# MCU_POWER.net
KiCad netlist of a schematic drawn in Altium Designer
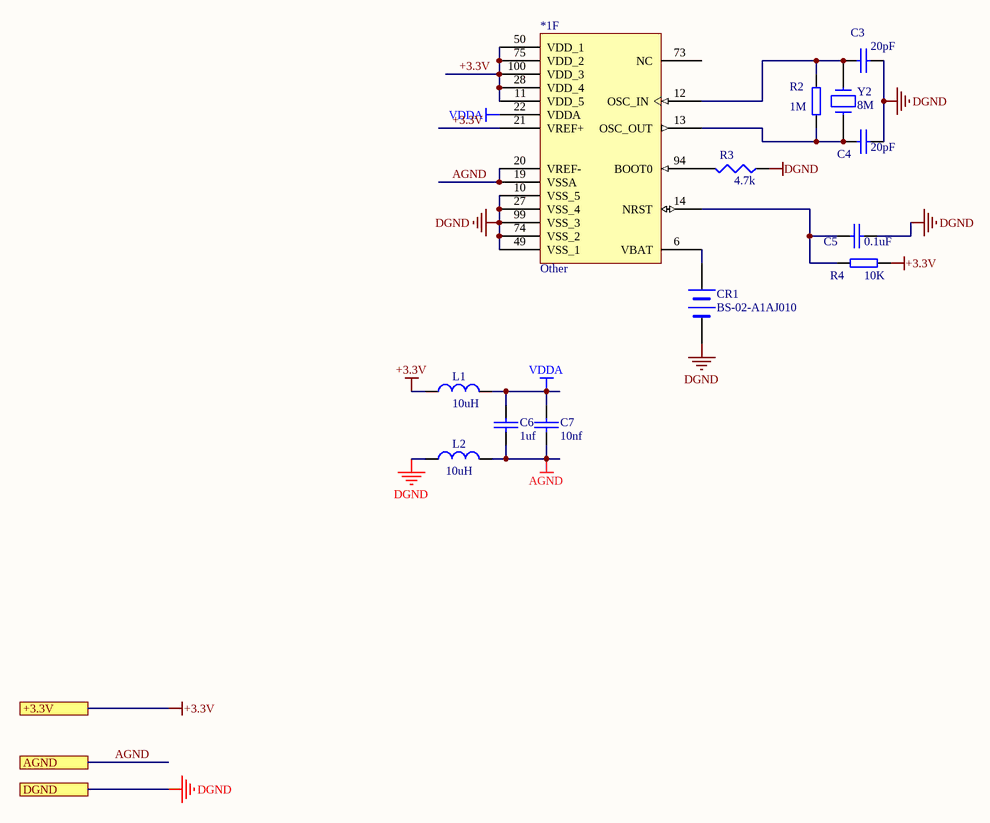
[diagram p0: MCU_POWER.SchDoc]

(export (version "E")
  (design (tool "Eeschema 10.0.6"))
  (components
    (comp (ref "*1")
      (value "Other")
      (footprint "STM-LQFP100_N")
      (libsource (lib "原理图") (part "stm32f103vct6"))
    )
    (comp (ref "C3")
      (value "20pF")
      (footprint "0805C")
      (description "品牌： SAMSUNG(三星)  型号： CL21C200JBANNNC     容值：20pF 精度：±5% 额定电压：50V 材质(温度系数)：C0G 材质:C0G")
      (libsource (lib "SCHPCBLIB ") (part "CAP_3"))
    )
    (comp (ref "C4")
      (value "20pF")
      (footprint "0805C")
      (description "品牌： SAMSUNG(三星)  型号： CL21C200JBANNNC     容值：20pF 精度：±5% 额定电压：50V 材质(温度系数)：C0G 材质:C0G")
      (libsource (lib "SCHPCBLIB ") (part "CAP_3"))
    )
    (comp (ref "C5")
      (value "0.1uF")
      (footprint "0805C")
      (description "品牌： SAMSUNG(三星)    型号： CL10B104KB8NNNC  容值：100nF 精度：±10% 额定电压：50V 材质(温度系数)：X7R 材质:X7R")
      (libsource (lib "SCHPCBLIB ") (part "CAP_3"))
    )
    (comp (ref "C6")
      (value "1uf")
      (footprint "0805C")
      (description "品牌： SAMSUNG(三星)  型号： CL21B105KBFNNNE  容值：1uF 精度：±10% 额定电压：50V 材质(温度系数)：X7R 材质:X7R")
      (libsource (lib "SCHPCBLIB ") (part "CAP_3"))
    )
    (comp (ref "C7")
      (value "10nf")
      (footprint "0805C")
      (description "品牌： SAMSUNG(三星)  型号： CL21B103KBANNNC  容值：10nF 精度：±10% 额定电压：50V 材质(温度系数)：X7R 材质:X7R")
      (libsource (lib "SCHPCBLIB ") (part "CAP_3"))
    )
    (comp (ref "CR1")
      (value "BS-02-A1AJ010")
      (footprint "BATT")
      (description "品牌： MYOUNG(美阳)  型号： BS-02-A1AJ010  连接器类型：电池底座 适用电池规格：CR2032 工作温度范围：-25℃~+85℃ 插脚 卧式底座 环保吸塑托盘包装")
      (libsource (lib "Documents") (part "BATTERY"))
    )
    (comp (ref "L1")
      (value "10uH")
      (footprint "L 0805")
      (description "品牌： FH(风华)  型号： CMI201209X100KT  ：电感值：10uH 精度：±10% 额定电流：15mA 直流电阻(DCR)：1.15Ω")
      (libsource (lib "SCHPCBLIB ") (part "INDUCTOR"))
    )
    (comp (ref "L2")
      (value "10uH")
      (footprint "L 0805")
      (description "品牌： FH(风华)  型号： CMI201209X100KT  ：电感值：10uH 精度：±10% 额定电流：15mA 直流电阻(DCR)：1.15Ω")
      (libsource (lib "SCHPCBLIB ") (part "INDUCTOR"))
    )
    (comp (ref "R2")
      (value "1M")
      (footprint "0805R")
      (description "品牌： UNI-ROYAL(厚声)  型号： 0805W8F1004T5E  电阻类型：厚膜电阻 阻值：1MΩ 精度：±1% 功率：125mW 温度系数：±100ppm/℃")
      (libsource (lib "SCHPCBLIB ") (part "RES4"))
    )
    (comp (ref "R3")
      (value "4.7k")
      (footprint "0805R")
      (description "品牌： UNI-ROYAL(厚声)  品牌： UNI-ROYAL(厚声)  电阻类型：厚膜电阻 阻值：100kΩ 精度：±1% 功率：125mW 温度系数：±100ppm/℃")
      (libsource (lib "*") (part "RES1"))
    )
    (comp (ref "R4")
      (value "10K")
      (footprint "0805R")
      (description "品牌： UNI-ROYAL(厚声) 型号： 0805W8F1002T5E 电阻类型：厚膜电阻 阻值：10kΩ 精度：±1% 功率：125mW 温度系数：±100ppm/℃")
      (libsource (lib "SCHPCBLIB ") (part "RES4"))
    )
    (comp (ref "Y2") (value "8M") (footprint "XTAL3") (libsource (lib "SCHPCBLIB ") (part "XTAL-1")))
  )
  (nets
    (net (code "1") (name "+3.3V") (class "Default")
      (node (ref "*1") (pin "100") (pinfunction "VDD_3_100") (pintype "power_in"))
      (node (ref "*1") (pin "11") (pinfunction "VDD_5_11") (pintype "power_in"))
      (node (ref "*1") (pin "21") (pinfunction "VREF+_21") (pintype "power_in"))
      (node (ref "*1") (pin "28") (pinfunction "VDD_4_28") (pintype "power_in"))
      (node (ref "*1") (pin "50") (pinfunction "VDD_1_50") (pintype "power_in"))
      (node (ref "*1") (pin "75") (pinfunction "VDD_2_75") (pintype "power_in"))
      (node (ref "L1") (pin "1") (pinfunction "1_1") (pintype "passive"))
      (node (ref "R4") (pin "2") (pinfunction "2_2") (pintype "passive"))
    )
    (net (code "2") (name "AGND") (class "Default")
      (node (ref "*1") (pin "19") (pinfunction "VSSA_19") (pintype "power_in"))
      (node (ref "*1") (pin "20") (pinfunction "VREF-_20") (pintype "power_in"))
      (node (ref "C6") (pin "1") (pinfunction "1_1") (pintype "passive"))
      (node (ref "C7") (pin "2") (pinfunction "2_2") (pintype "passive"))
      (node (ref "L2") (pin "2") (pinfunction "2_2") (pintype "passive"))
    )
    (net (code "3") (name "DGND") (class "Default")
      (node (ref "*1") (pin "10") (pinfunction "VSS_5_10") (pintype "power_in"))
      (node (ref "*1") (pin "27") (pinfunction "VSS_4_27") (pintype "power_in"))
      (node (ref "*1") (pin "49") (pinfunction "VSS_1_49") (pintype "power_in"))
      (node (ref "*1") (pin "74") (pinfunction "VSS_2_74") (pintype "power_in"))
      (node (ref "*1") (pin "99") (pinfunction "VSS_3_99") (pintype "power_in"))
      (node (ref "C3") (pin "2") (pinfunction "2_2") (pintype "passive"))
      (node (ref "C4") (pin "2") (pinfunction "2_2") (pintype "passive"))
      (node (ref "C5") (pin "1") (pinfunction "1_1") (pintype "passive"))
      (node (ref "CR1") (pin "2") (pinfunction "-_2") (pintype "passive"))
      (node (ref "L2") (pin "1") (pinfunction "1_1") (pintype "passive"))
      (node (ref "R3") (pin "1") (pinfunction "1_1") (pintype "passive"))
    )
    (net (code "4") (name "Net-(*1F-BOOT0)") (class "Default")
      (node (ref "*1") (pin "94") (pinfunction "BOOT0_94") (pintype "input"))
      (node (ref "R3") (pin "2") (pinfunction "2_2") (pintype "passive"))
    )
    (net (code "5") (name "Net-(*1F-NRST)") (class "Default")
      (node (ref "*1") (pin "14") (pinfunction "NRST_14") (pintype "bidirectional"))
      (node (ref "C5") (pin "2") (pinfunction "2_2") (pintype "passive"))
      (node (ref "R4") (pin "1") (pinfunction "1_1") (pintype "passive"))
    )
    (net (code "6") (name "Net-(*1F-OSC_IN)") (class "Default")
      (node (ref "*1") (pin "12") (pinfunction "OSC_IN_12") (pintype "input"))
      (node (ref "C3") (pin "1") (pinfunction "1_1") (pintype "passive"))
      (node (ref "R2") (pin "1") (pinfunction "1_1") (pintype "passive"))
      (node (ref "Y2") (pin "1") (pinfunction "1_1") (pintype "passive"))
    )
    (net (code "7") (name "Net-(*1F-OSC_OUT)") (class "Default")
      (node (ref "*1") (pin "13") (pinfunction "OSC_OUT_13") (pintype "output"))
      (node (ref "C4") (pin "1") (pinfunction "1_1") (pintype "passive"))
      (node (ref "R2") (pin "2") (pinfunction "2_2") (pintype "passive"))
      (node (ref "Y2") (pin "2") (pinfunction "2_2") (pintype "passive"))
    )
    (net (code "8") (name "Net-(*1F-VBAT)") (class "Default")
      (node (ref "*1") (pin "6") (pinfunction "VBAT_6") (pintype "power_in"))
      (node (ref "CR1") (pin "1") (pinfunction "+_1") (pintype "passive"))
    )
    (net (code "9") (name "VDDA") (class "Default")
      (node (ref "*1") (pin "22") (pinfunction "VDDA_22") (pintype "power_in"))
      (node (ref "C6") (pin "2") (pinfunction "2_2") (pintype "passive"))
      (node (ref "C7") (pin "1") (pinfunction "1_1") (pintype "passive"))
      (node (ref "L1") (pin "2") (pinfunction "2_2") (pintype "passive"))
    )
    (net (code "10") (name "unconnected-(*1F-NC-Pad73)") (class "Default")
      (node (ref "*1") (pin "73") (pinfunction "NC_73") (pintype "passive"))
    )
  )
)
